# SOIC14-TSSOP14.net
KiCad netlist of a schematic drawn in EAGLE
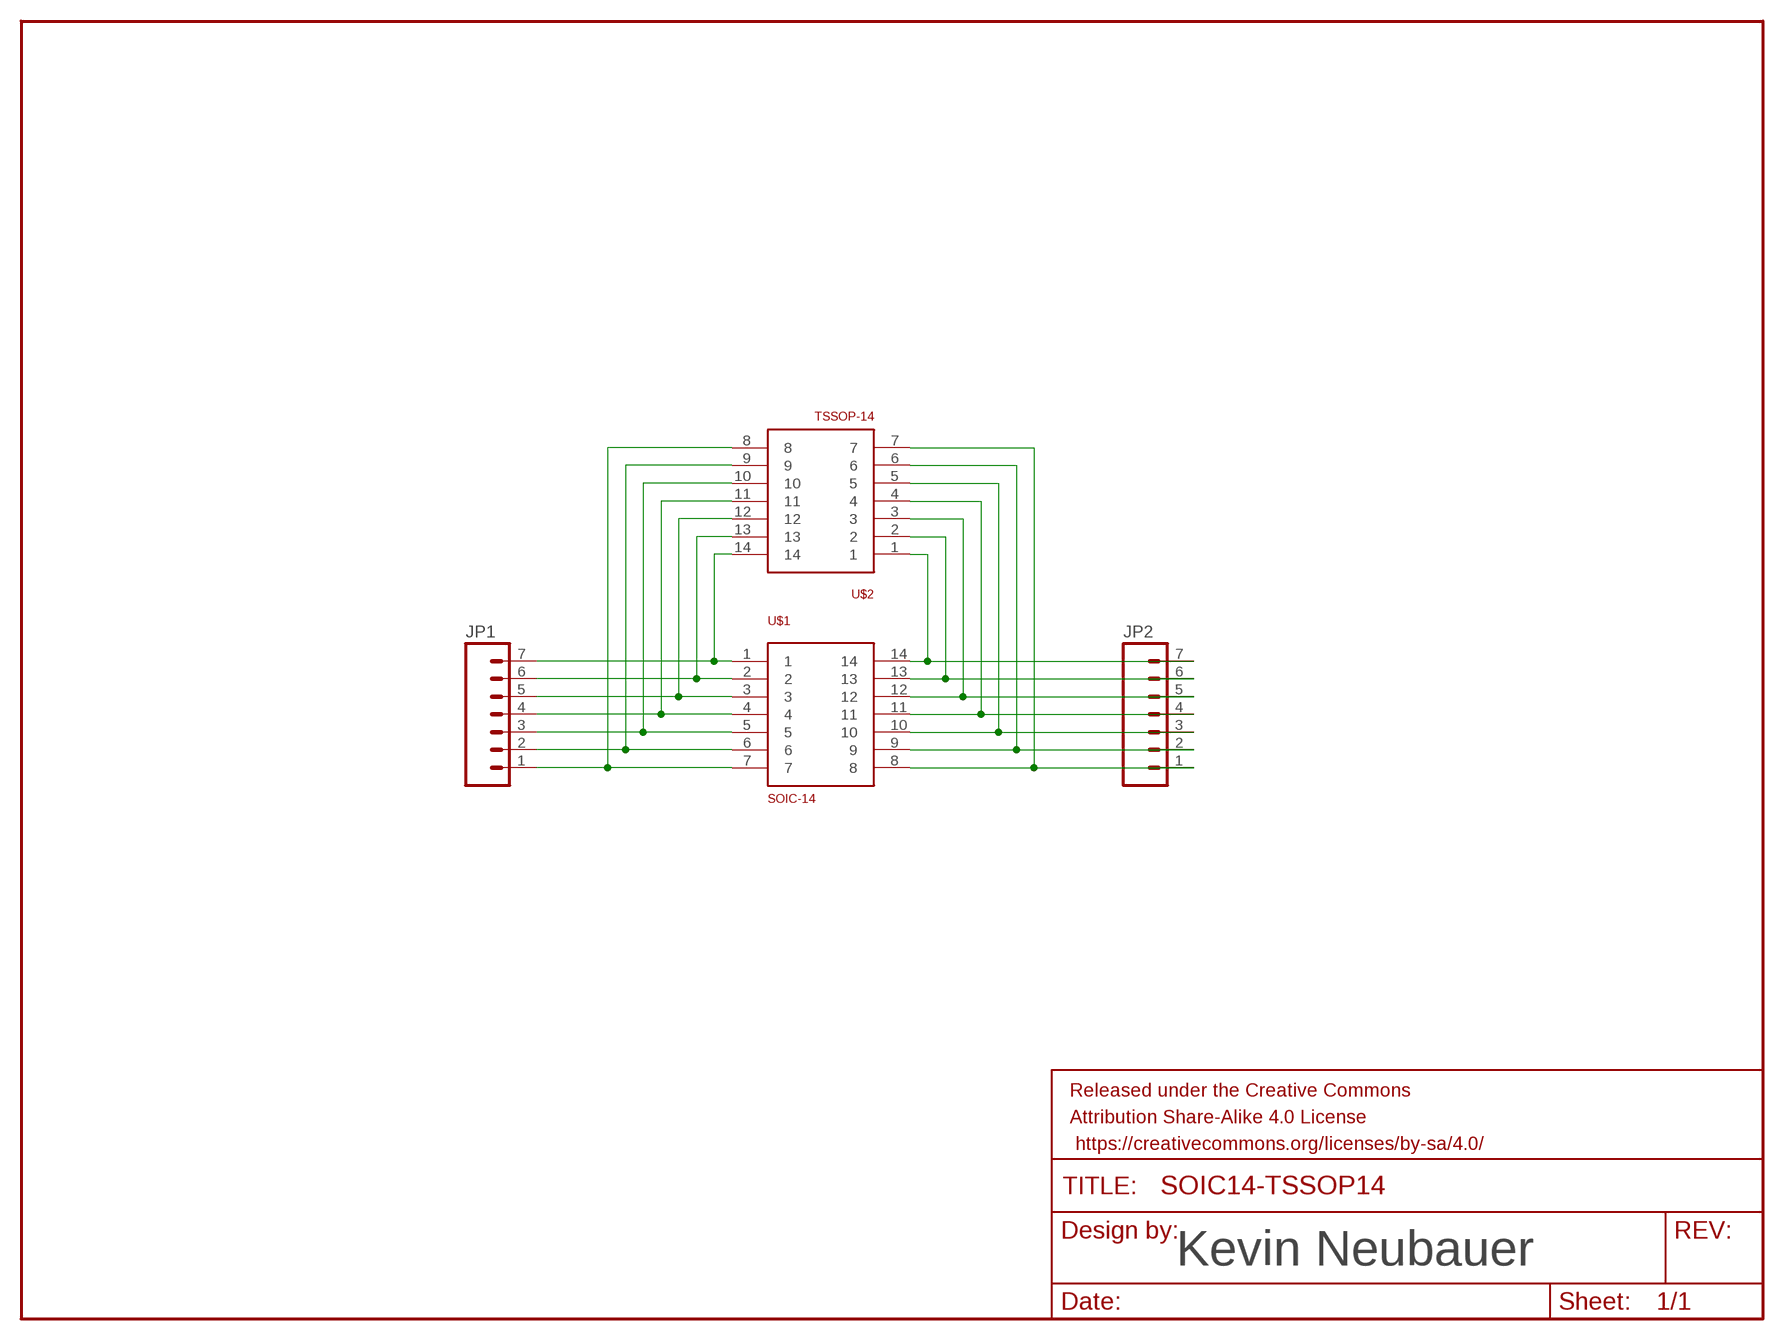
[diagram p0: schematic, sheet 1]

(export (version "E")
  (design (tool "Eeschema 10.0.6"))
  (components
    (comp (ref "FRAME1")
      (value "FRAME-LETTER")
      (footprint "eagle-import:CREATIVE_COMMONS")
      (libsource (lib "eagle-import") (part "FRAME-LETTER"))
    )
    (comp (ref "JP1")
      (value "M07")
      (footprint "eagle-import:1X07")
      (libsource (lib "eagle-import") (part "M07"))
    )
    (comp (ref "JP2")
      (value "M07")
      (footprint "eagle-import:1X07")
      (libsource (lib "eagle-import") (part "M07"))
    )
    (comp (ref "U$1")
      (value "SOIC-14")
      (footprint "eagle-import:SOIC-14")
      (libsource (lib "eagle-import") (part "SOIC-14"))
    )
    (comp (ref "U$2")
      (value "TSSOP-14")
      (footprint "eagle-import:TSSOP14")
      (libsource (lib "eagle-import") (part "TSSOP-14"))
    )
  )
  (nets
    (net (code "1") (name "Net-(JP1-Pad1)") (class "Default")
      (node (ref "JP1") (pin "1") (pinfunction "1_1") (pintype "passive"))
      (node (ref "U$1") (pin "7") (pinfunction "7_7") (pintype "bidirectional"))
      (node (ref "U$2") (pin "8") (pinfunction "8_8") (pintype "bidirectional"))
    )
    (net (code "2") (name "Net-(JP1-Pad2)") (class "Default")
      (node (ref "JP1") (pin "2") (pinfunction "2_2") (pintype "passive"))
      (node (ref "U$1") (pin "6") (pinfunction "6_6") (pintype "bidirectional"))
      (node (ref "U$2") (pin "9") (pinfunction "9_9") (pintype "bidirectional"))
    )
    (net (code "3") (name "Net-(JP1-Pad3)") (class "Default")
      (node (ref "JP1") (pin "3") (pinfunction "3_3") (pintype "passive"))
      (node (ref "U$1") (pin "5") (pinfunction "5_5") (pintype "bidirectional"))
      (node (ref "U$2") (pin "10") (pinfunction "10_10") (pintype "bidirectional"))
    )
    (net (code "4") (name "Net-(JP1-Pad4)") (class "Default")
      (node (ref "JP1") (pin "4") (pinfunction "4_4") (pintype "passive"))
      (node (ref "U$1") (pin "4") (pinfunction "4_4") (pintype "bidirectional"))
      (node (ref "U$2") (pin "11") (pinfunction "11_11") (pintype "bidirectional"))
    )
    (net (code "5") (name "Net-(JP1-Pad5)") (class "Default")
      (node (ref "JP1") (pin "5") (pinfunction "5_5") (pintype "passive"))
      (node (ref "U$1") (pin "3") (pinfunction "3_3") (pintype "bidirectional"))
      (node (ref "U$2") (pin "12") (pinfunction "12_12") (pintype "bidirectional"))
    )
    (net (code "6") (name "Net-(JP1-Pad6)") (class "Default")
      (node (ref "JP1") (pin "6") (pinfunction "6_6") (pintype "passive"))
      (node (ref "U$1") (pin "2") (pinfunction "2_2") (pintype "bidirectional"))
      (node (ref "U$2") (pin "13") (pinfunction "13_13") (pintype "bidirectional"))
    )
    (net (code "7") (name "Net-(JP1-Pad7)") (class "Default")
      (node (ref "JP1") (pin "7") (pinfunction "7_7") (pintype "passive"))
      (node (ref "U$1") (pin "1") (pinfunction "1_1") (pintype "bidirectional"))
      (node (ref "U$2") (pin "14") (pinfunction "14_14") (pintype "bidirectional"))
    )
    (net (code "8") (name "Net-(JP2-Pad1)") (class "Default")
      (node (ref "JP2") (pin "1") (pinfunction "1_1") (pintype "passive"))
      (node (ref "U$1") (pin "8") (pinfunction "8_8") (pintype "bidirectional"))
      (node (ref "U$2") (pin "7") (pinfunction "7_7") (pintype "bidirectional"))
    )
    (net (code "9") (name "Net-(JP2-Pad2)") (class "Default")
      (node (ref "JP2") (pin "2") (pinfunction "2_2") (pintype "passive"))
      (node (ref "U$1") (pin "9") (pinfunction "9_9") (pintype "bidirectional"))
      (node (ref "U$2") (pin "6") (pinfunction "6_6") (pintype "bidirectional"))
    )
    (net (code "10") (name "Net-(JP2-Pad3)") (class "Default")
      (node (ref "JP2") (pin "3") (pinfunction "3_3") (pintype "passive"))
      (node (ref "U$1") (pin "10") (pinfunction "10_10") (pintype "bidirectional"))
      (node (ref "U$2") (pin "5") (pinfunction "5_5") (pintype "bidirectional"))
    )
    (net (code "11") (name "Net-(JP2-Pad4)") (class "Default")
      (node (ref "JP2") (pin "4") (pinfunction "4_4") (pintype "passive"))
      (node (ref "U$1") (pin "11") (pinfunction "11_11") (pintype "bidirectional"))
      (node (ref "U$2") (pin "4") (pinfunction "4_4") (pintype "bidirectional"))
    )
    (net (code "12") (name "Net-(JP2-Pad5)") (class "Default")
      (node (ref "JP2") (pin "5") (pinfunction "5_5") (pintype "passive"))
      (node (ref "U$1") (pin "12") (pinfunction "12_12") (pintype "bidirectional"))
      (node (ref "U$2") (pin "3") (pinfunction "3_3") (pintype "bidirectional"))
    )
    (net (code "13") (name "Net-(JP2-Pad6)") (class "Default")
      (node (ref "JP2") (pin "6") (pinfunction "6_6") (pintype "passive"))
      (node (ref "U$1") (pin "13") (pinfunction "13_13") (pintype "bidirectional"))
      (node (ref "U$2") (pin "2") (pinfunction "2_2") (pintype "bidirectional"))
    )
    (net (code "14") (name "Net-(JP2-Pad7)") (class "Default")
      (node (ref "JP2") (pin "7") (pinfunction "7_7") (pintype "passive"))
      (node (ref "U$1") (pin "14") (pinfunction "14_14") (pintype "bidirectional"))
      (node (ref "U$2") (pin "1") (pinfunction "1_1") (pintype "bidirectional"))
    )
  )
)
